# CONNECTOR_IN.net
KiCad netlist of a schematic drawn in Altium Designer
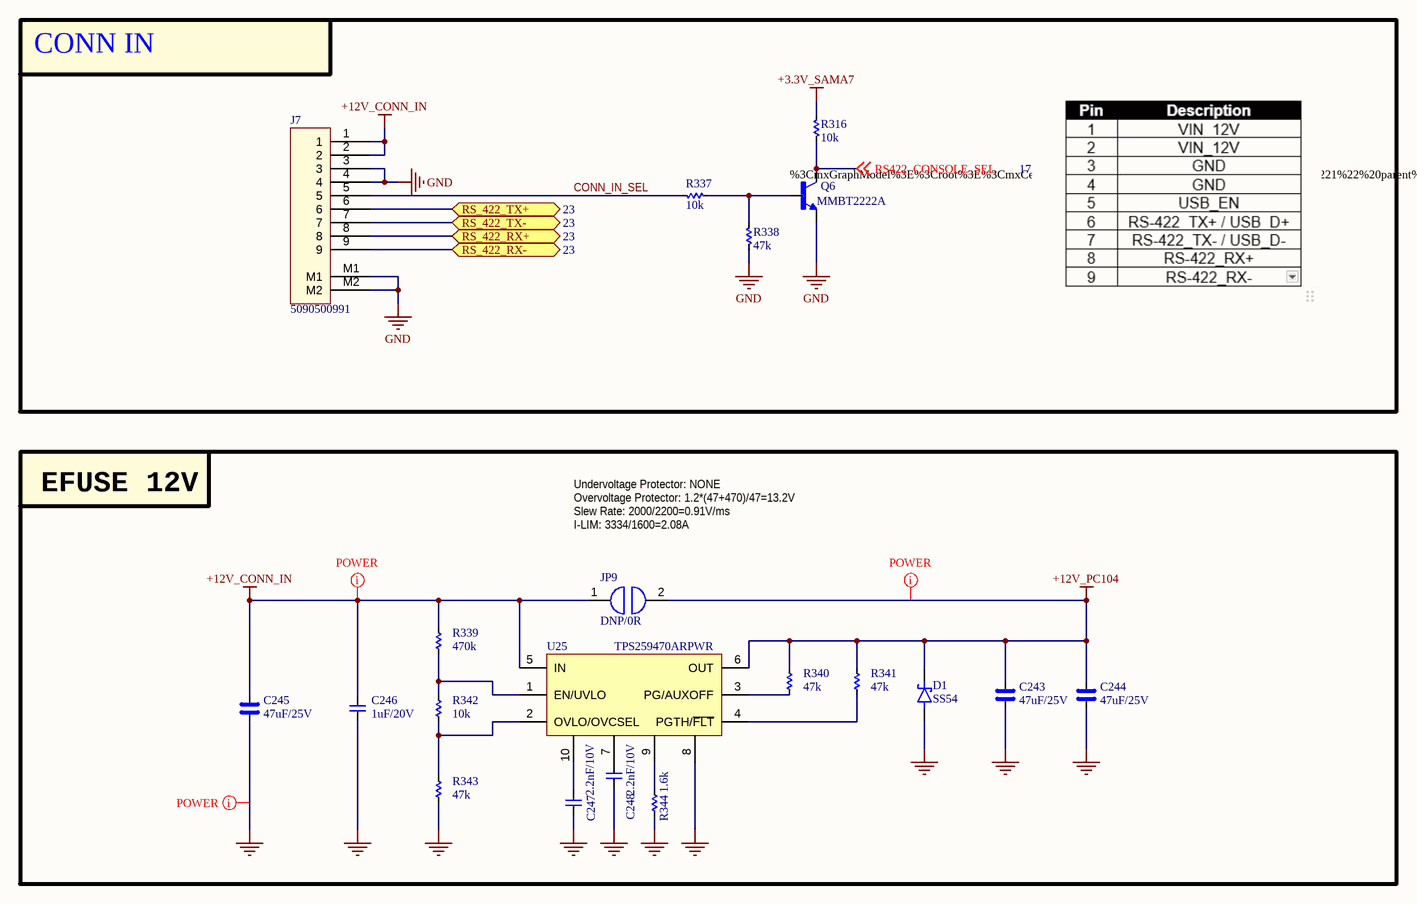
[diagram p0: CONNECTOR_IN.SchDoc]

(export (version "E")
  (design (tool "Eeschema 10.0.6"))
  (components
    (comp (ref "C243")
      (value "47uF/25V")
      (footprint "CAP_C_3225X80")
      (description "CAP High Value")
      (libsource (lib "LABLIB") (part "_CAP_C_High_2"))
    )
    (comp (ref "C244")
      (value "47uF/25V")
      (footprint "CAP_C_3225X80")
      (description "CAP High Value")
      (libsource (lib "LABLIB") (part "_CAP_C_High_2"))
    )
    (comp (ref "C245")
      (value "47uF/25V")
      (footprint "CAP_C_3225X80")
      (description "CAP High Value")
      (libsource (lib "LABLIB") (part "_CAP_C_High_2"))
    )
    (comp (ref "C246")
      (value "1uF/20V")
      (footprint "CAP_C_1005X50_L")
      (description "CAP")
      (libsource (lib "LABLIB") (part "_CAP_C_2"))
    )
    (comp (ref "C247")
      (value "2.2nF/10V")
      (footprint "CAP_C_1005X50_L")
      (description "CAP")
      (libsource (lib "LABLIB") (part "_CAP_C_2"))
    )
    (comp (ref "C248")
      (value "2.2nF/10V")
      (footprint "CAP_C_1005X50_L")
      (description "CAP")
      (libsource (lib "LABLIB") (part "_CAP_C_2"))
    )
    (comp (ref "D1")
      (value "SS54")
      (footprint "DO-214AC_SMA")
      (description "DIODE SCHOTTKY")
      (libsource (lib "LABLIB") (part "DIODE SCHOTTKY"))
    )
    (comp (ref "J7")
      (value "5090500991")
      (footprint "MOLEX_5040500991")
      (libsource (lib "LABLIB") (part "Header 9x1_2M"))
    )
    (comp (ref "JP9") (value "DNP/0R") (footprint "JUMPER_1608") (libsource (lib "EXP_V1") (part "JUMPER")))
    (comp (ref "Q6")
      (value "MMBT2222A")
      (footprint "SOT95P240X120-3N")
      (fields (field (name "MF") "Diotec Semiconductor"))
      (libsource (lib "LABLIB") (part "BJT_NPN_BEC"))
    )
    (comp (ref "R316")
      (value "10k")
      (footprint "RES_C_1005x30_L")
      (description "RES")
      (libsource (lib "LABLIB") (part "_RES_B_2"))
    )
    (comp (ref "R337")
      (value "10k")
      (footprint "RES_C_1005x30_L")
      (description "RES")
      (libsource (lib "LABLIB") (part "_RES_B_2"))
    )
    (comp (ref "R338")
      (value "47k")
      (footprint "RES_C_1005x30_L")
      (description "RES")
      (libsource (lib "IFBschelib") (part "_RES_B_2"))
    )
    (comp (ref "R339")
      (value "470k")
      (footprint "RES_C_1005x30_L")
      (description "RES")
      (libsource (lib "LABLIB") (part "_RES_B_2"))
    )
    (comp (ref "R340")
      (value "47k")
      (footprint "RES_C_1005x30_L")
      (description "RES")
      (libsource (lib "LABLIB") (part "_RES_B_2"))
    )
    (comp (ref "R341")
      (value "47k")
      (footprint "RES_C_1005x30_L")
      (description "RES")
      (libsource (lib "LABLIB") (part "_RES_B_2"))
    )
    (comp (ref "R342")
      (value "10k")
      (footprint "RES_C_1005x30_L")
      (description "RES")
      (libsource (lib "LABLIB") (part "_RES_B_2"))
    )
    (comp (ref "R343")
      (value "47k")
      (footprint "RES_C_1005x30_L")
      (description "RES")
      (libsource (lib "LABLIB") (part "_RES_B_2"))
    )
    (comp (ref "R344")
      (value "1.6k")
      (footprint "RES_C_1005x30_L")
      (description "RES")
      (libsource (lib "LABLIB") (part "_RES_B_2"))
    )
    (comp (ref "U25")
      (value "TPS259470ARPWR")
      (footprint "VQFN-HR-10")
      (libsource (lib "EXP_HW_V3") (part "TPS259470ARPWR"))
    )
  )
  (nets
    (net (code "1") (name "+3.3V_SAMA7") (class "Default")
      (node (ref "R316") (pin "2") (pinfunction "2_2") (pintype "passive"))
    )
    (net (code "2") (name "+12V_CONN_IN") (class "Default")
      (node (ref "C245") (pin "2") (pinfunction "2_2") (pintype "passive"))
      (node (ref "C246") (pin "2") (pinfunction "2_2") (pintype "passive"))
      (node (ref "J7") (pin "1") (pinfunction "1_1") (pintype "passive"))
      (node (ref "J7") (pin "2") (pinfunction "2_2") (pintype "passive"))
      (node (ref "JP9") (pin "1") (pinfunction "1_1") (pintype "passive"))
      (node (ref "R339") (pin "2") (pinfunction "2_2") (pintype "passive"))
      (node (ref "U25") (pin "5") (pinfunction "IN_5") (pintype "passive"))
    )
    (net (code "3") (name "+12V_PC104") (class "Default")
      (node (ref "C243") (pin "2") (pinfunction "2_2") (pintype "passive"))
      (node (ref "C244") (pin "2") (pinfunction "2_2") (pintype "passive"))
      (node (ref "D1") (pin "1") (pinfunction "K_1") (pintype "passive"))
      (node (ref "JP9") (pin "2") (pinfunction "2_2") (pintype "passive"))
      (node (ref "R340") (pin "2") (pinfunction "2_2") (pintype "passive"))
      (node (ref "R341") (pin "2") (pinfunction "2_2") (pintype "passive"))
      (node (ref "U25") (pin "6") (pinfunction "OUT_6") (pintype "passive"))
    )
    (net (code "4") (name "/CONN_IN_SEL") (class "Default")
      (node (ref "J7") (pin "5") (pinfunction "5_5") (pintype "passive"))
      (node (ref "R337") (pin "1") (pinfunction "1_1") (pintype "passive"))
    )
    (net (code "5") (name "/RS_422_RX+") (class "Default")
      (node (ref "J7") (pin "8") (pinfunction "8_8") (pintype "passive"))
    )
    (net (code "6") (name "/RS_422_RX-") (class "Default")
      (node (ref "J7") (pin "9") (pinfunction "9_9") (pintype "passive"))
    )
    (net (code "7") (name "/RS_422_TX+") (class "Default")
      (node (ref "J7") (pin "6") (pinfunction "6_6") (pintype "passive"))
    )
    (net (code "8") (name "/RS_422_TX-") (class "Default")
      (node (ref "J7") (pin "7") (pinfunction "7_7") (pintype "passive"))
    )
    (net (code "9") (name "GND") (class "Default")
      (node (ref "C243") (pin "1") (pinfunction "1_1") (pintype "passive"))
      (node (ref "C244") (pin "1") (pinfunction "1_1") (pintype "passive"))
      (node (ref "C245") (pin "1") (pinfunction "1_1") (pintype "passive"))
      (node (ref "C246") (pin "1") (pinfunction "1_1") (pintype "passive"))
      (node (ref "C247") (pin "1") (pinfunction "1_1") (pintype "passive"))
      (node (ref "C248") (pin "1") (pinfunction "1_1") (pintype "passive"))
      (node (ref "D1") (pin "2") (pinfunction "A_2") (pintype "passive"))
      (node (ref "J7") (pin "3") (pinfunction "3_3") (pintype "passive"))
      (node (ref "J7") (pin "4") (pinfunction "4_4") (pintype "passive"))
      (node (ref "J7") (pin "M1") (pinfunction "M1_M1") (pintype "passive"))
      (node (ref "J7") (pin "M2") (pinfunction "M2_M2") (pintype "passive"))
      (node (ref "Q6") (pin "2") (pinfunction "E_2") (pintype "passive"))
      (node (ref "R338") (pin "1") (pinfunction "1_1") (pintype "passive"))
      (node (ref "R343") (pin "1") (pinfunction "1_1") (pintype "passive"))
      (node (ref "R344") (pin "1") (pinfunction "1_1") (pintype "passive"))
      (node (ref "U25") (pin "8") (pinfunction "8_8") (pintype "passive"))
    )
    (net (code "10") (name "Net-(C247-Pad2)") (class "Default")
      (node (ref "C247") (pin "2") (pinfunction "2_2") (pintype "passive"))
      (node (ref "U25") (pin "10") (pinfunction "10_10") (pintype "passive"))
    )
    (net (code "11") (name "Net-(C248-Pad2)") (class "Default")
      (node (ref "C248") (pin "2") (pinfunction "2_2") (pintype "passive"))
      (node (ref "U25") (pin "7") (pinfunction "7_7") (pintype "passive"))
    )
    (net (code "12") (name "Net-(Q6-B)") (class "Default")
      (node (ref "Q6") (pin "1") (pinfunction "B_1") (pintype "passive"))
      (node (ref "R337") (pin "2") (pinfunction "2_2") (pintype "passive"))
      (node (ref "R338") (pin "2") (pinfunction "2_2") (pintype "passive"))
    )
    (net (code "13") (name "Net-(R344-Pad2)") (class "Default")
      (node (ref "R344") (pin "2") (pinfunction "2_2") (pintype "passive"))
      (node (ref "U25") (pin "9") (pinfunction "9_9") (pintype "passive"))
    )
    (net (code "14") (name "Net-(U25-EN{slash}UVLO)") (class "Default")
      (node (ref "R339") (pin "1") (pinfunction "1_1") (pintype "passive"))
      (node (ref "R342") (pin "1") (pinfunction "1_1") (pintype "passive"))
      (node (ref "U25") (pin "1") (pinfunction "EN/UVLO_1") (pintype "passive"))
    )
    (net (code "15") (name "Net-(U25-OVLO{slash}OVCSEL)") (class "Default")
      (node (ref "R342") (pin "2") (pinfunction "2_2") (pintype "passive"))
      (node (ref "R343") (pin "2") (pinfunction "2_2") (pintype "passive"))
      (node (ref "U25") (pin "2") (pinfunction "OVLO/OVCSEL_2") (pintype "passive"))
    )
    (net (code "16") (name "Net-(U25-PGTH{slash}~{FLT})") (class "Default")
      (node (ref "R341") (pin "1") (pinfunction "1_1") (pintype "passive"))
      (node (ref "U25") (pin "4") (pinfunction "PGTH/~{FLT}_4") (pintype "passive"))
    )
    (net (code "17") (name "Net-(U25-PG{slash}AUXOFF)") (class "Default")
      (node (ref "R340") (pin "1") (pinfunction "1_1") (pintype "passive"))
      (node (ref "U25") (pin "3") (pinfunction "PG/AUXOFF_3") (pintype "passive"))
    )
    (net (code "18") (name "RS422_CONSOLE_SEL") (class "Default")
      (node (ref "Q6") (pin "3") (pinfunction "C_3") (pintype "passive"))
      (node (ref "R316") (pin "1") (pinfunction "1_1") (pintype "passive"))
    )
  )
)
